# SOM_CAN.net
KiCad netlist of a schematic drawn in Altium Designer
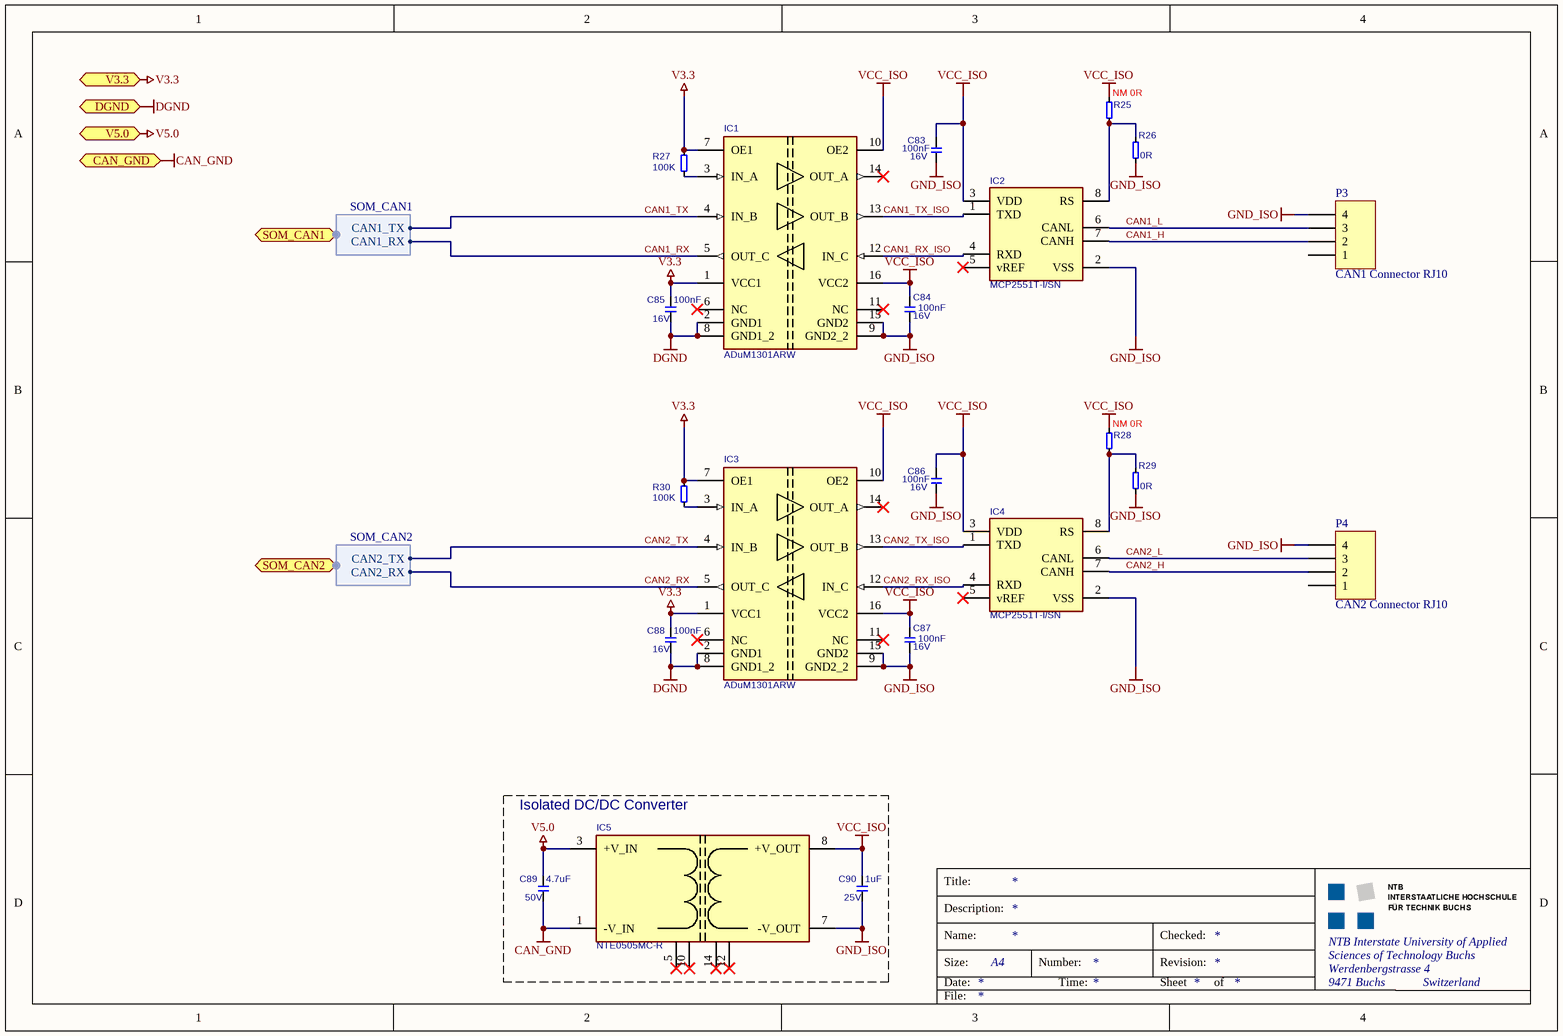
[diagram p0: SOM_CAN.SchDoc]

(export (version "E")
  (design (tool "Eeschema 10.0.6"))
  (components
    (comp (ref "C83")
      (value "100nF")
      (footprint "0603_3D")
      (description "Capacitor Ceramic X7R 100nF 16V 10% 0603")
      (fields (field (name "TOLERANCE") "10%") (field (name "RATING") "16V"))
      (libsource (lib "Evaluation Board") (part "C-X7R-100nF-16V-10%-0603"))
    )
    (comp (ref "C84")
      (value "100nF")
      (footprint "0603_3D")
      (description "Capacitor Ceramic X7R 100nF 16V 10% 0603")
      (fields (field (name "TOLERANCE") "10%") (field (name "RATING") "16V"))
      (libsource (lib "Evaluation Board") (part "C-X7R-100nF-16V-10%-0603"))
    )
    (comp (ref "C85")
      (value "100nF")
      (footprint "0603_3D")
      (description "Capacitor Ceramic X7R 100nF 16V 10% 0603")
      (fields (field (name "TOLERANCE") "10%") (field (name "RATING") "16V"))
      (libsource (lib "Evaluation Board") (part "C-X7R-100nF-16V-10%-0603"))
    )
    (comp (ref "C86")
      (value "100nF")
      (footprint "0603_3D")
      (description "Capacitor Ceramic X7R 100nF 16V 10% 0603")
      (fields (field (name "TOLERANCE") "10%") (field (name "RATING") "16V"))
      (libsource (lib "Evaluation Board") (part "C-X7R-100nF-16V-10%-0603"))
    )
    (comp (ref "C87")
      (value "100nF")
      (footprint "0603_3D")
      (description "Capacitor Ceramic X7R 100nF 16V 10% 0603")
      (fields (field (name "TOLERANCE") "10%") (field (name "RATING") "16V"))
      (libsource (lib "Evaluation Board") (part "C-X7R-100nF-16V-10%-0603"))
    )
    (comp (ref "C88")
      (value "100nF")
      (footprint "0603_3D")
      (description "Capacitor Ceramic X7R 100nF 16V 10% 0603")
      (fields (field (name "TOLERANCE") "10%") (field (name "RATING") "16V"))
      (libsource (lib "Evaluation Board") (part "C-X7R-100nF-16V-10%-0603"))
    )
    (comp (ref "C89")
      (value "4.7uF")
      (footprint "1206")
      (description "Capacitor Ceramic X7R 100nF 16V 10% 0603")
      (fields (field (name "TOLERANCE") "10%") (field (name "RATING") "50V"))
      (libsource (lib "Evaluation Board") (part "C-X7R-100nF-16V-10%-0603"))
    )
    (comp (ref "C90")
      (value "1uF")
      (footprint "0603_3D")
      (description "Capacitor Ceramic X7R 100nF 16V 10% 0603")
      (fields (field (name "TOLERANCE") "10%") (field (name "RATING") "25V"))
      (libsource (lib "Evaluation Board") (part "C-X7R-100nF-16V-10%-0603"))
    )
    (comp (ref "IC1")
      (value "ADuM1301ARW")
      (footprint "T_AD_ADuM1300ARW")
      (description "Digital Isolator")
      (fields (field (name "MANUFACTURER PART NO.") "ADuM1301ARW"))
      (libsource (lib "Evaluation Board") (part "IC-AD-ADuM1301ARW"))
    )
    (comp (ref "IC2")
      (value "MCP2551T-I/SN")
      (footprint "SOIC127P600X173-8N")
      (description "High speed CAN Transceiver")
      (fields (field (name "MANUFACTURER PART NO.") "MCP2551T-I/SN"))
      (libsource (lib "Evaluation Board") (part "IC-MC-MCP2551T-I/SN"))
    )
    (comp (ref "IC3")
      (value "ADuM1301ARW")
      (footprint "T_AD_ADuM1300ARW")
      (description "Digital Isolator")
      (fields (field (name "MANUFACTURER PART NO.") "ADuM1301ARW"))
      (libsource (lib "Evaluation Board") (part "IC-AD-ADuM1301ARW"))
    )
    (comp (ref "IC4")
      (value "MCP2551T-I/SN")
      (footprint "SOIC127P600X173-8N")
      (description "High speed CAN Transceiver")
      (fields (field (name "MANUFACTURER PART NO.") "MCP2551T-I/SN"))
      (libsource (lib "Evaluation Board") (part "IC-MC-MCP2551T-I/SN"))
    )
    (comp (ref "IC5")
      (value "NTE0505MC-R")
      (footprint "T_MURATA_NTE0505MC-R")
      (description "Isolated DC/DC Converter")
      (fields (field (name "MANUFACTURER PART NO.") "NTE0505MC-R"))
      (libsource (lib "Evaluation Board") (part "IC-MUR-NTE0505MC-R"))
    )
    (comp (ref "P3")
      (value "CAN1 Connector RJ10")
      (footprint "95009-2447")
      (description "Header, 4-Pin")
      (fields (field (name "PUBLISHER") "Altium Limited"))
      (libsource (lib "Miscellaneous Connectors") (part "Header 4"))
    )
    (comp (ref "P4")
      (value "CAN2 Connector RJ10")
      (footprint "95009-2447")
      (description "Header, 4-Pin")
      (fields (field (name "PUBLISHER") "Altium Limited"))
      (libsource (lib "Miscellaneous Connectors") (part "Header 4"))
    )
    (comp (ref "R25")
      (value "NM 0R")
      (footprint "0603_3D")
      (description "Resistor 0 ohm 63mW 1% 0603")
      (fields (field (name "TOLERANCE") "1%"))
      (libsource (lib "Evaluation Board") (part "R-0R-63mW-1%-0603"))
    )
    (comp (ref "R26")
      (value "0R")
      (footprint "0603_3D")
      (description "Resistor 0 ohm 63mW 1% 0603")
      (fields (field (name "TOLERANCE") "1%"))
      (libsource (lib "Evaluation Board") (part "R-0R-63mW-1%-0603"))
    )
    (comp (ref "R27")
      (value "100K")
      (footprint "0603_3D")
      (description "Resistor 100 Kohm 63mW 5% 0603")
      (fields (field (name "TOLERANCE") "5%"))
      (libsource (lib "Evaluation Board") (part "R-100KR-63mW-5%-0603"))
    )
    (comp (ref "R28")
      (value "NM 0R")
      (footprint "0603_3D")
      (description "Resistor 0 ohm 63mW 1% 0603")
      (fields (field (name "TOLERANCE") "1%"))
      (libsource (lib "Evaluation Board") (part "R-0R-63mW-1%-0603"))
    )
    (comp (ref "R29")
      (value "0R")
      (footprint "0603_3D")
      (description "Resistor 0 ohm 63mW 1% 0603")
      (fields (field (name "TOLERANCE") "1%"))
      (libsource (lib "Evaluation Board") (part "R-0R-63mW-1%-0603"))
    )
    (comp (ref "R30")
      (value "100K")
      (footprint "0603_3D")
      (description "Resistor 100 Kohm 63mW 5% 0603")
      (fields (field (name "TOLERANCE") "5%"))
      (libsource (lib "Evaluation Board") (part "R-100KR-63mW-5%-0603"))
    )
  )
  (nets
    (net (code "3") (name "/CAN1_H") (class "Default")
      (node (ref "IC2") (pin "7") (pinfunction "CANH_7") (pintype "passive"))
      (node (ref "P3") (pin "2") (pinfunction "2_2") (pintype "passive"))
    )
    (net (code "4") (name "/CAN1_L") (class "Default")
      (node (ref "IC2") (pin "6") (pinfunction "CANL_6") (pintype "passive"))
      (node (ref "P3") (pin "3") (pinfunction "3_3") (pintype "passive"))
    )
    (net (code "5") (name "/CAN1_RX") (class "Default")
      (node (ref "IC1") (pin "5") (pinfunction "OUT_C_5") (pintype "output"))
    )
    (net (code "6") (name "/CAN1_RX_ISO") (class "Default")
      (node (ref "IC1") (pin "12") (pinfunction "IN_C_12") (pintype "input"))
      (node (ref "IC2") (pin "4") (pinfunction "RXD_4") (pintype "passive"))
    )
    (net (code "7") (name "/CAN1_TX") (class "Default")
      (node (ref "IC1") (pin "4") (pinfunction "IN_B_4") (pintype "input"))
    )
    (net (code "8") (name "/CAN1_TX_ISO") (class "Default")
      (node (ref "IC1") (pin "13") (pinfunction "OUT_B_13") (pintype "output"))
      (node (ref "IC2") (pin "1") (pinfunction "TXD_1") (pintype "passive"))
    )
    (net (code "9") (name "/CAN2_H") (class "Default")
      (node (ref "IC4") (pin "7") (pinfunction "CANH_7") (pintype "passive"))
      (node (ref "P4") (pin "2") (pinfunction "2_2") (pintype "passive"))
    )
    (net (code "10") (name "/CAN2_L") (class "Default")
      (node (ref "IC4") (pin "6") (pinfunction "CANL_6") (pintype "passive"))
      (node (ref "P4") (pin "3") (pinfunction "3_3") (pintype "passive"))
    )
    (net (code "11") (name "/CAN2_RX") (class "Default")
      (node (ref "IC3") (pin "5") (pinfunction "OUT_C_5") (pintype "output"))
    )
    (net (code "12") (name "/CAN2_RX_ISO") (class "Default")
      (node (ref "IC3") (pin "12") (pinfunction "IN_C_12") (pintype "input"))
      (node (ref "IC4") (pin "4") (pinfunction "RXD_4") (pintype "passive"))
    )
    (net (code "13") (name "/CAN2_TX") (class "Default")
      (node (ref "IC3") (pin "4") (pinfunction "IN_B_4") (pintype "input"))
    )
    (net (code "14") (name "/CAN2_TX_ISO") (class "Default")
      (node (ref "IC3") (pin "13") (pinfunction "OUT_B_13") (pintype "output"))
      (node (ref "IC4") (pin "1") (pinfunction "TXD_1") (pintype "passive"))
    )
    (net (code "17") (name "CAN_GND") (class "Default")
      (node (ref "C89") (pin "1") (pinfunction "1_1") (pintype "passive"))
      (node (ref "IC5") (pin "1") (pinfunction "-V_IN_1") (pintype "power_in"))
    )
    (net (code "18") (name "DGND") (class "Default")
      (node (ref "C85") (pin "1") (pinfunction "1_1") (pintype "passive"))
      (node (ref "C88") (pin "1") (pinfunction "1_1") (pintype "passive"))
      (node (ref "IC1") (pin "2") (pinfunction "GND1_2") (pintype "power_in"))
      (node (ref "IC1") (pin "8") (pinfunction "GND1_2_8") (pintype "power_in"))
      (node (ref "IC3") (pin "2") (pinfunction "GND1_2") (pintype "power_in"))
      (node (ref "IC3") (pin "8") (pinfunction "GND1_2_8") (pintype "power_in"))
    )
    (net (code "19") (name "GND_ISO") (class "Default")
      (node (ref "C83") (pin "1") (pinfunction "1_1") (pintype "passive"))
      (node (ref "C84") (pin "1") (pinfunction "1_1") (pintype "passive"))
      (node (ref "C86") (pin "1") (pinfunction "1_1") (pintype "passive"))
      (node (ref "C87") (pin "1") (pinfunction "1_1") (pintype "passive"))
      (node (ref "C90") (pin "1") (pinfunction "1_1") (pintype "passive"))
      (node (ref "IC1") (pin "15") (pinfunction "GND2_15") (pintype "power_in"))
      (node (ref "IC1") (pin "9") (pinfunction "GND2_2_9") (pintype "power_in"))
      (node (ref "IC2") (pin "2") (pinfunction "VSS_2") (pintype "passive"))
      (node (ref "IC3") (pin "15") (pinfunction "GND2_15") (pintype "power_in"))
      (node (ref "IC3") (pin "9") (pinfunction "GND2_2_9") (pintype "power_in"))
      (node (ref "IC4") (pin "2") (pinfunction "VSS_2") (pintype "passive"))
      (node (ref "IC5") (pin "7") (pinfunction "-V_OUT_7") (pintype "power_in"))
      (node (ref "P3") (pin "4") (pinfunction "4_4") (pintype "passive"))
      (node (ref "P4") (pin "4") (pinfunction "4_4") (pintype "passive"))
      (node (ref "R26") (pin "1") (pinfunction "1_1") (pintype "passive"))
      (node (ref "R29") (pin "1") (pinfunction "1_1") (pintype "passive"))
    )
    (net (code "20") (name "Net-(IC1-IN_A)") (class "Default")
      (node (ref "IC1") (pin "3") (pinfunction "IN_A_3") (pintype "input"))
      (node (ref "R27") (pin "1") (pinfunction "1_1") (pintype "passive"))
    )
    (net (code "21") (name "Net-(IC2-RS)") (class "Default")
      (node (ref "IC2") (pin "8") (pinfunction "RS_8") (pintype "passive"))
      (node (ref "R25") (pin "1") (pinfunction "1_1") (pintype "passive"))
      (node (ref "R26") (pin "2") (pinfunction "2_2") (pintype "passive"))
    )
    (net (code "22") (name "Net-(IC3-IN_A)") (class "Default")
      (node (ref "IC3") (pin "3") (pinfunction "IN_A_3") (pintype "input"))
      (node (ref "R30") (pin "1") (pinfunction "1_1") (pintype "passive"))
    )
    (net (code "23") (name "Net-(IC4-RS)") (class "Default")
      (node (ref "IC4") (pin "8") (pinfunction "RS_8") (pintype "passive"))
      (node (ref "R28") (pin "1") (pinfunction "1_1") (pintype "passive"))
      (node (ref "R29") (pin "2") (pinfunction "2_2") (pintype "passive"))
    )
    (net (code "24") (name "V3.3") (class "Default")
      (node (ref "C85") (pin "2") (pinfunction "2_2") (pintype "passive"))
      (node (ref "C88") (pin "2") (pinfunction "2_2") (pintype "passive"))
      (node (ref "IC1") (pin "1") (pinfunction "VCC1_1") (pintype "passive"))
      (node (ref "IC1") (pin "7") (pinfunction "OE1_7") (pintype "passive"))
      (node (ref "IC3") (pin "1") (pinfunction "VCC1_1") (pintype "passive"))
      (node (ref "IC3") (pin "7") (pinfunction "OE1_7") (pintype "passive"))
      (node (ref "R27") (pin "2") (pinfunction "2_2") (pintype "passive"))
      (node (ref "R30") (pin "2") (pinfunction "2_2") (pintype "passive"))
    )
    (net (code "25") (name "V5.0") (class "Default")
      (node (ref "C89") (pin "2") (pinfunction "2_2") (pintype "passive"))
      (node (ref "IC5") (pin "3") (pinfunction "+V_IN_3") (pintype "power_in"))
    )
    (net (code "26") (name "VCC_ISO") (class "Default")
      (node (ref "C83") (pin "2") (pinfunction "2_2") (pintype "passive"))
      (node (ref "C84") (pin "2") (pinfunction "2_2") (pintype "passive"))
      (node (ref "C86") (pin "2") (pinfunction "2_2") (pintype "passive"))
      (node (ref "C87") (pin "2") (pinfunction "2_2") (pintype "passive"))
      (node (ref "C90") (pin "2") (pinfunction "2_2") (pintype "passive"))
      (node (ref "IC1") (pin "10") (pinfunction "OE2_10") (pintype "passive"))
      (node (ref "IC1") (pin "16") (pinfunction "VCC2_16") (pintype "passive"))
      (node (ref "IC2") (pin "3") (pinfunction "VDD_3") (pintype "passive"))
      (node (ref "IC3") (pin "10") (pinfunction "OE2_10") (pintype "passive"))
      (node (ref "IC3") (pin "16") (pinfunction "VCC2_16") (pintype "passive"))
      (node (ref "IC4") (pin "3") (pinfunction "VDD_3") (pintype "passive"))
      (node (ref "IC5") (pin "8") (pinfunction "+V_OUT_8") (pintype "power_in"))
      (node (ref "R25") (pin "2") (pinfunction "2_2") (pintype "passive"))
      (node (ref "R28") (pin "2") (pinfunction "2_2") (pintype "passive"))
    )
    (net (code "27") (name "unconnected-(IC1-NC-Pad6)") (class "Default")
      (node (ref "IC1") (pin "6") (pinfunction "NC_6") (pintype "passive+no_connect"))
    )
    (net (code "28") (name "unconnected-(IC1-NC-Pad11)") (class "Default")
      (node (ref "IC1") (pin "11") (pinfunction "NC_11") (pintype "passive+no_connect"))
    )
    (net (code "29") (name "unconnected-(IC1-OUT_A-Pad14)") (class "Default")
      (node (ref "IC1") (pin "14") (pinfunction "OUT_A_14") (pintype "output+no_connect"))
    )
    (net (code "30") (name "unconnected-(IC2-vREF-Pad5)") (class "Default")
      (node (ref "IC2") (pin "5") (pinfunction "vREF_5") (pintype "passive+no_connect"))
    )
    (net (code "31") (name "unconnected-(IC3-NC-Pad6)") (class "Default")
      (node (ref "IC3") (pin "6") (pinfunction "NC_6") (pintype "passive+no_connect"))
    )
    (net (code "32") (name "unconnected-(IC3-NC-Pad11)") (class "Default")
      (node (ref "IC3") (pin "11") (pinfunction "NC_11") (pintype "passive+no_connect"))
    )
    (net (code "33") (name "unconnected-(IC3-OUT_A-Pad14)") (class "Default")
      (node (ref "IC3") (pin "14") (pinfunction "OUT_A_14") (pintype "output+no_connect"))
    )
    (net (code "34") (name "unconnected-(IC4-vREF-Pad5)") (class "Default")
      (node (ref "IC4") (pin "5") (pinfunction "vREF_5") (pintype "passive+no_connect"))
    )
    (net (code "35") (name "unconnected-(IC5-NC-Pad5)") (class "Default")
      (node (ref "IC5") (pin "5") (pinfunction "NC_5") (pintype "passive+no_connect"))
    )
    (net (code "36") (name "unconnected-(IC5-NC-Pad10)") (class "Default")
      (node (ref "IC5") (pin "10") (pinfunction "NC_10") (pintype "passive+no_connect"))
    )
    (net (code "37") (name "unconnected-(IC5-NC-Pad12)") (class "Default")
      (node (ref "IC5") (pin "12") (pinfunction "NC_12") (pintype "passive+no_connect"))
    )
    (net (code "38") (name "unconnected-(IC5-NC-Pad14)") (class "Default")
      (node (ref "IC5") (pin "14") (pinfunction "NC_14") (pintype "passive+no_connect"))
    )
    (net (code "39") (name "unconnected-(P3-Pad1)") (class "Default")
      (node (ref "P3") (pin "1") (pinfunction "1_1") (pintype "passive"))
    )
    (net (code "40") (name "unconnected-(P4-Pad1)") (class "Default")
      (node (ref "P4") (pin "1") (pinfunction "1_1") (pintype "passive"))
    )
  )
)
